# LIS344ALH-old.net
KiCad netlist of a schematic drawn in EAGLE
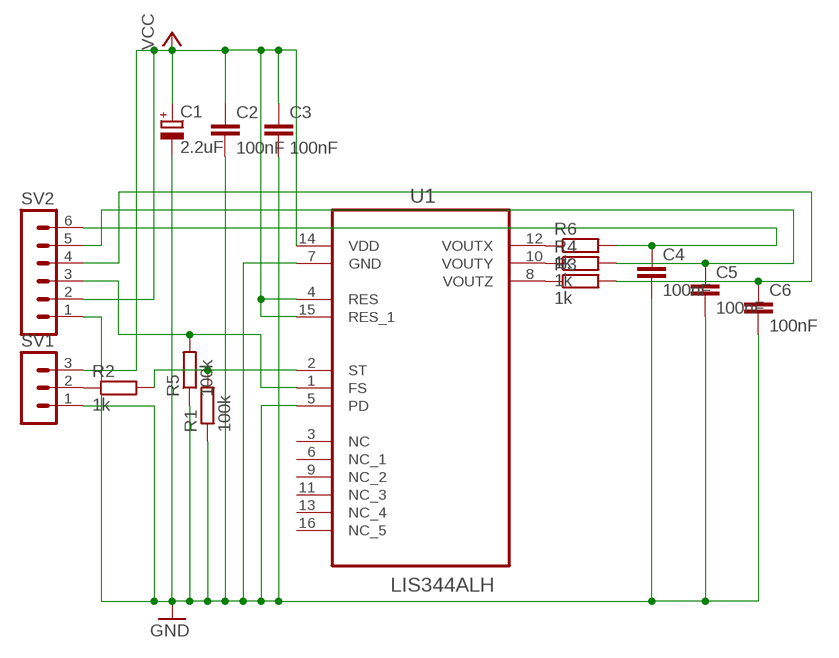
[diagram p0: schematic, sheet 1]

(export (version "E")
  (design (tool "Eeschema 10.0.6"))
  (components
    (comp (ref "C1")
      (value "2.2uF")
      (footprint "eagle-import:E2,5-6E")
      (libsource (lib "eagle-import") (part "CPOL-EUE2,5-6E"))
    )
    (comp (ref "C2")
      (value "100nF")
      (footprint "eagle-import:C2.5-2")
      (libsource (lib "eagle-import") (part "C2.5/2"))
    )
    (comp (ref "C3")
      (value "100nF")
      (footprint "eagle-import:C2.5-2")
      (libsource (lib "eagle-import") (part "C2.5/2"))
    )
    (comp (ref "C4")
      (value "100nF")
      (footprint "eagle-import:C2.5-2")
      (libsource (lib "eagle-import") (part "C2.5/2"))
    )
    (comp (ref "C5")
      (value "100nF")
      (footprint "eagle-import:C2.5-2")
      (libsource (lib "eagle-import") (part "C2.5/2"))
    )
    (comp (ref "C6")
      (value "100nF")
      (footprint "eagle-import:C2.5-2")
      (libsource (lib "eagle-import") (part "C2.5/2"))
    )
    (comp (ref "R1")
      (value "100k")
      (footprint "eagle-import:0204_7")
      (libsource (lib "eagle-import") (part "R-EU_0204/7"))
    )
    (comp (ref "R2")
      (value "1k")
      (footprint "eagle-import:0204_7")
      (libsource (lib "eagle-import") (part "R-EU_0204/7"))
    )
    (comp (ref "R3")
      (value "1k")
      (footprint "eagle-import:0204_7")
      (libsource (lib "eagle-import") (part "R-EU_0204/7"))
    )
    (comp (ref "R4")
      (value "1k")
      (footprint "eagle-import:0204_7")
      (libsource (lib "eagle-import") (part "R-EU_0204/7"))
    )
    (comp (ref "R5")
      (value "100k")
      (footprint "eagle-import:0204_7")
      (libsource (lib "eagle-import") (part "R-EU_0204/7"))
    )
    (comp (ref "R6")
      (value "1k")
      (footprint "eagle-import:0204_7")
      (libsource (lib "eagle-import") (part "R-EU_0204/7"))
    )
    (comp (ref "SV1")
      (value "MA03-1")
      (footprint "eagle-import:MA03-1")
      (libsource (lib "eagle-import") (part "MA03-1"))
    )
    (comp (ref "SV2")
      (value "MA06-1")
      (footprint "eagle-import:MA06-1")
      (libsource (lib "eagle-import") (part "MA06-1"))
    )
    (comp (ref "U1")
      (value "LIS344ALH")
      (footprint "eagle-import:LGA16R65P4X4_400X400X160")
      (fields (field (name "MF") "STMicroelectronics"))
      (libsource (lib "eagle-import") (part "LIS344ALH"))
    )
  )
  (nets
    (net (code "1") (name "GND") (class "Default")
      (node (ref "C1") (pin "-") (pinfunction "-_-") (pintype "passive"))
      (node (ref "C2") (pin "2") (pinfunction "2_2") (pintype "passive"))
      (node (ref "C3") (pin "2") (pinfunction "2_2") (pintype "passive"))
      (node (ref "C4") (pin "2") (pinfunction "2_2") (pintype "passive"))
      (node (ref "C5") (pin "2") (pinfunction "2_2") (pintype "passive"))
      (node (ref "C6") (pin "2") (pinfunction "2_2") (pintype "passive"))
      (node (ref "R1") (pin "1") (pinfunction "1_1") (pintype "passive"))
      (node (ref "R5") (pin "1") (pinfunction "1_1") (pintype "passive"))
      (node (ref "SV1") (pin "1") (pinfunction "1_1") (pintype "passive"))
      (node (ref "SV2") (pin "1") (pinfunction "1_1") (pintype "passive"))
      (node (ref "U1") (pin "5") (pinfunction "PD_5") (pintype "passive"))
      (node (ref "U1") (pin "7") (pinfunction "GND_7") (pintype "passive"))
    )
    (net (code "2") (name "Net-(C4-Pad1)") (class "Default")
      (node (ref "C4") (pin "1") (pinfunction "1_1") (pintype "passive"))
      (node (ref "R6") (pin "2") (pinfunction "2_2") (pintype "passive"))
      (node (ref "SV2") (pin "6") (pinfunction "6_6") (pintype "passive"))
    )
    (net (code "3") (name "Net-(C5-Pad1)") (class "Default")
      (node (ref "C5") (pin "1") (pinfunction "1_1") (pintype "passive"))
      (node (ref "R4") (pin "2") (pinfunction "2_2") (pintype "passive"))
      (node (ref "SV2") (pin "5") (pinfunction "5_5") (pintype "passive"))
    )
    (net (code "4") (name "Net-(C6-Pad1)") (class "Default")
      (node (ref "C6") (pin "1") (pinfunction "1_1") (pintype "passive"))
      (node (ref "R3") (pin "2") (pinfunction "2_2") (pintype "passive"))
      (node (ref "SV2") (pin "4") (pinfunction "4_4") (pintype "passive"))
    )
    (net (code "5") (name "Net-(R2-Pad1)") (class "Default")
      (node (ref "R2") (pin "1") (pinfunction "1_1") (pintype "passive"))
      (node (ref "SV1") (pin "2") (pinfunction "2_2") (pintype "passive"))
    )
    (net (code "6") (name "Net-(U1-FS)") (class "Default")
      (node (ref "R5") (pin "2") (pinfunction "2_2") (pintype "passive"))
      (node (ref "SV2") (pin "3") (pinfunction "3_3") (pintype "passive"))
      (node (ref "U1") (pin "1") (pinfunction "FS_1") (pintype "passive"))
    )
    (net (code "7") (name "Net-(U1-ST)") (class "Default")
      (node (ref "R1") (pin "2") (pinfunction "2_2") (pintype "passive"))
      (node (ref "R2") (pin "2") (pinfunction "2_2") (pintype "passive"))
      (node (ref "U1") (pin "2") (pinfunction "ST_2") (pintype "passive"))
    )
    (net (code "8") (name "Net-(U1-VOUTX)") (class "Default")
      (node (ref "R6") (pin "1") (pinfunction "1_1") (pintype "passive"))
      (node (ref "U1") (pin "12") (pinfunction "VOUTX_12") (pintype "output"))
    )
    (net (code "9") (name "Net-(U1-VOUTY)") (class "Default")
      (node (ref "R4") (pin "1") (pinfunction "1_1") (pintype "passive"))
      (node (ref "U1") (pin "10") (pinfunction "VOUTY_10") (pintype "output"))
    )
    (net (code "10") (name "Net-(U1-VOUTZ)") (class "Default")
      (node (ref "R3") (pin "1") (pinfunction "1_1") (pintype "passive"))
      (node (ref "U1") (pin "8") (pinfunction "VOUTZ_8") (pintype "output"))
    )
    (net (code "11") (name "VCC") (class "Default")
      (node (ref "C1") (pin "+") (pinfunction "+_+") (pintype "passive"))
      (node (ref "C2") (pin "1") (pinfunction "1_1") (pintype "passive"))
      (node (ref "C3") (pin "1") (pinfunction "1_1") (pintype "passive"))
      (node (ref "SV1") (pin "3") (pinfunction "3_3") (pintype "passive"))
      (node (ref "SV2") (pin "2") (pinfunction "2_2") (pintype "passive"))
      (node (ref "U1") (pin "14") (pinfunction "VDD_14") (pintype "power_in"))
      (node (ref "U1") (pin "15") (pinfunction "RES_1_15") (pintype "passive"))
      (node (ref "U1") (pin "4") (pinfunction "RES_4") (pintype "passive"))
    )
    (net (code "12") (name "unconnected-(U1-NC-Pad3)") (class "Default")
      (node (ref "U1") (pin "3") (pinfunction "NC_3") (pintype "no_connect"))
    )
    (net (code "13") (name "unconnected-(U1-NC_1-Pad6)") (class "Default")
      (node (ref "U1") (pin "6") (pinfunction "NC_1_6") (pintype "no_connect"))
    )
    (net (code "14") (name "unconnected-(U1-NC_2-Pad9)") (class "Default")
      (node (ref "U1") (pin "9") (pinfunction "NC_2_9") (pintype "no_connect"))
    )
    (net (code "15") (name "unconnected-(U1-NC_3-Pad11)") (class "Default")
      (node (ref "U1") (pin "11") (pinfunction "NC_3_11") (pintype "no_connect"))
    )
    (net (code "16") (name "unconnected-(U1-NC_4-Pad13)") (class "Default")
      (node (ref "U1") (pin "13") (pinfunction "NC_4_13") (pintype "no_connect"))
    )
    (net (code "17") (name "unconnected-(U1-NC_5-Pad16)") (class "Default")
      (node (ref "U1") (pin "16") (pinfunction "NC_5_16") (pintype "no_connect"))
    )
  )
)
